# 6_CLOCK.net
KiCad netlist of a schematic drawn in Altium Designer
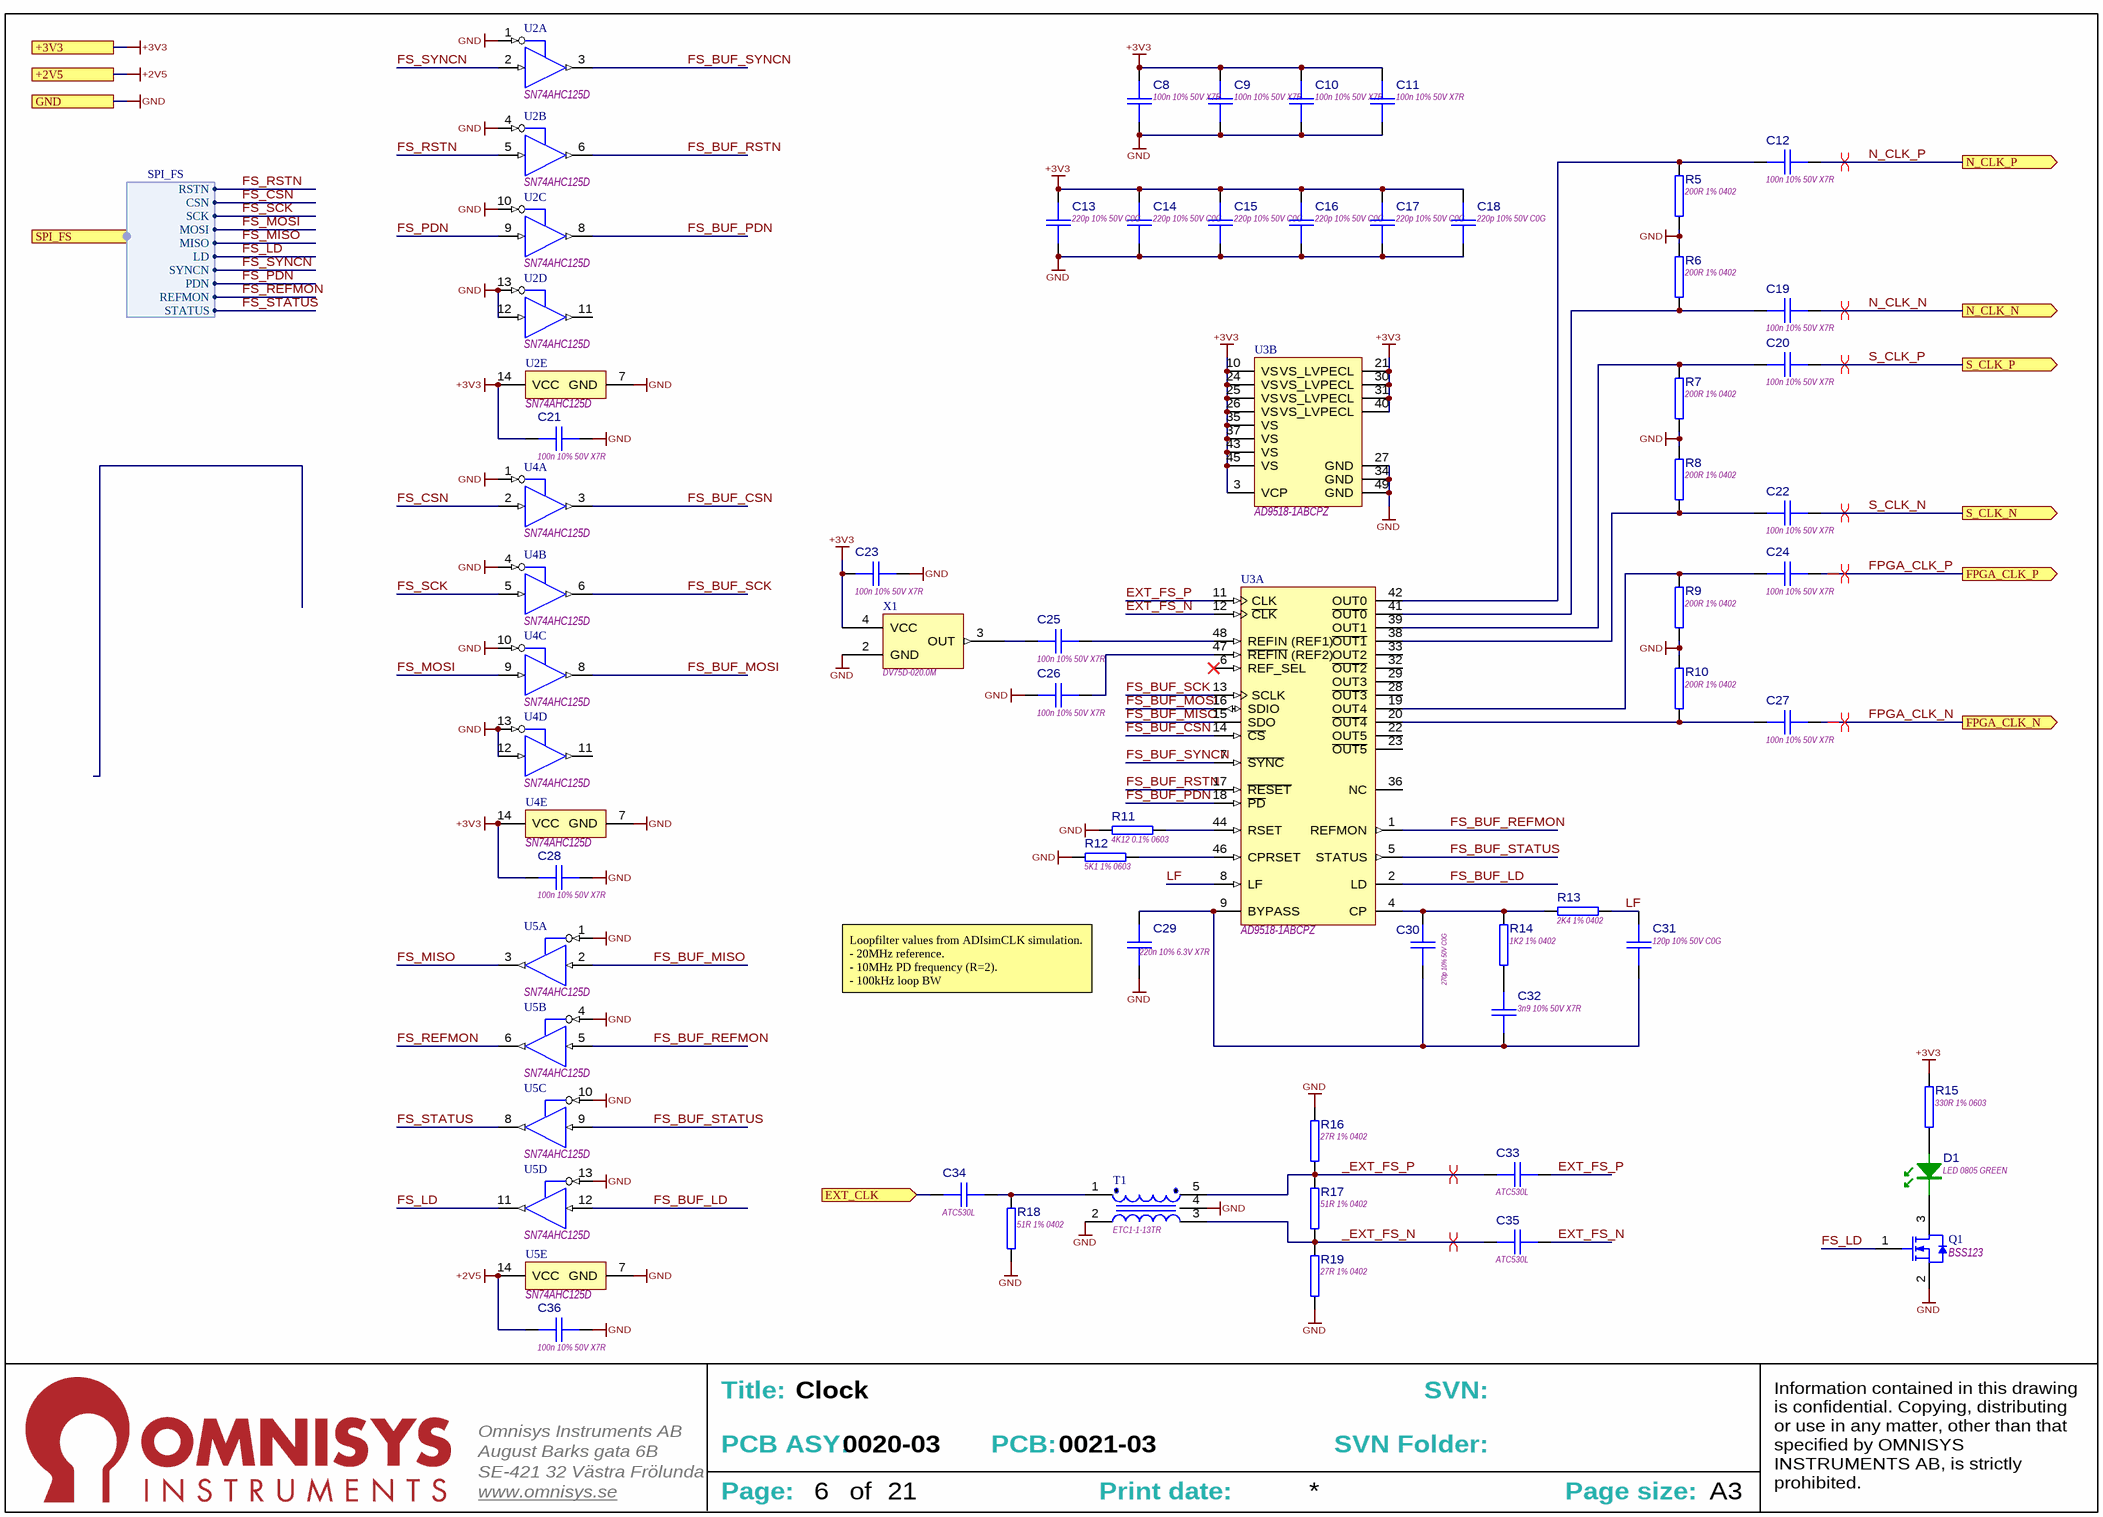
[diagram p0: [6] CLOCK.SchDoc]

(export (version "E")
  (design (tool "Eeschema 10.0.6"))
  (components
    (comp (ref "C8")
      (value "100n 10% 50V X7R")
      (footprint "CAPC1608X90N")
      (description "Ceramic Chip Capacitor, 0603/1608")
      (fields (field (name "TOLERANCE") "10%"))
      (libsource (lib "Omnisys Vault") (part "CAP-2PIN"))
    )
    (comp (ref "C9")
      (value "100n 10% 50V X7R")
      (footprint "CAPC1608X90N")
      (description "Ceramic Chip Capacitor, 0603/1608")
      (fields (field (name "TOLERANCE") "10%"))
      (libsource (lib "Omnisys Vault") (part "CAP-2PIN"))
    )
    (comp (ref "C10")
      (value "100n 10% 50V X7R")
      (footprint "CAPC1608X90N")
      (description "Ceramic Chip Capacitor, 0603/1608")
      (fields (field (name "TOLERANCE") "10%"))
      (libsource (lib "Omnisys Vault") (part "CAP-2PIN"))
    )
    (comp (ref "C11")
      (value "100n 10% 50V X7R")
      (footprint "CAPC1608X90N")
      (description "Ceramic Chip Capacitor, 0603/1608")
      (fields (field (name "TOLERANCE") "10%"))
      (libsource (lib "Omnisys Vault") (part "CAP-2PIN"))
    )
    (comp (ref "C12")
      (value "100n 10% 50V X7R")
      (footprint "CAPC1005X55L")
      (description "Ceramic Chip Capacitor, 0402/1005")
      (fields (field (name "TOLERANCE") "10%"))
      (libsource (lib "Omnisys Vault") (part "CAP-2PIN"))
    )
    (comp (ref "C13")
      (value "220p 10% 50V C0G")
      (footprint "CAPC1005X55N")
      (description "Ceramic Chip Capacitor, 0402/1005")
      (fields (field (name "TOLERANCE") "10%"))
      (libsource (lib "Omnisys Vault") (part "CAP-2PIN"))
    )
    (comp (ref "C14")
      (value "220p 10% 50V C0G")
      (footprint "CAPC1005X55N")
      (description "Ceramic Chip Capacitor, 0402/1005")
      (fields (field (name "TOLERANCE") "10%"))
      (libsource (lib "Omnisys Vault") (part "CAP-2PIN"))
    )
    (comp (ref "C15")
      (value "220p 10% 50V C0G")
      (footprint "CAPC1005X55N")
      (description "Ceramic Chip Capacitor, 0402/1005")
      (fields (field (name "TOLERANCE") "10%"))
      (libsource (lib "Omnisys Vault") (part "CAP-2PIN"))
    )
    (comp (ref "C16")
      (value "220p 10% 50V C0G")
      (footprint "CAPC1005X55N")
      (description "Ceramic Chip Capacitor, 0402/1005")
      (fields (field (name "TOLERANCE") "10%"))
      (libsource (lib "Omnisys Vault") (part "CAP-2PIN"))
    )
    (comp (ref "C17")
      (value "220p 10% 50V C0G")
      (footprint "CAPC1005X55N")
      (description "Ceramic Chip Capacitor, 0402/1005")
      (fields (field (name "TOLERANCE") "10%"))
      (libsource (lib "Omnisys Vault") (part "CAP-2PIN"))
    )
    (comp (ref "C18")
      (value "220p 10% 50V C0G")
      (footprint "CAPC1005X55N")
      (description "Ceramic Chip Capacitor, 0402/1005")
      (fields (field (name "TOLERANCE") "10%"))
      (libsource (lib "Omnisys Vault") (part "CAP-2PIN"))
    )
    (comp (ref "C19")
      (value "100n 10% 50V X7R")
      (footprint "CAPC1005X55L")
      (description "Ceramic Chip Capacitor, 0402/1005")
      (fields (field (name "TOLERANCE") "10%"))
      (libsource (lib "Omnisys Vault") (part "CAP-2PIN"))
    )
    (comp (ref "C20")
      (value "100n 10% 50V X7R")
      (footprint "CAPC1005X55L")
      (description "Ceramic Chip Capacitor, 0402/1005")
      (fields (field (name "TOLERANCE") "10%"))
      (libsource (lib "Omnisys Vault") (part "CAP-2PIN"))
    )
    (comp (ref "C21")
      (value "100n 10% 50V X7R")
      (footprint "CAPC1608X90N")
      (description "Ceramic Chip Capacitor, 0603/1608")
      (fields (field (name "TOLERANCE") "10%"))
      (libsource (lib "Omnisys Vault") (part "CAP-2PIN"))
    )
    (comp (ref "C22")
      (value "100n 10% 50V X7R")
      (footprint "CAPC1005X55L")
      (description "Ceramic Chip Capacitor, 0402/1005")
      (fields (field (name "TOLERANCE") "10%"))
      (libsource (lib "Omnisys Vault") (part "CAP-2PIN"))
    )
    (comp (ref "C23")
      (value "100n 10% 50V X7R")
      (footprint "CAPC1608X90N")
      (description "Ceramic Chip Capacitor, 0603/1608")
      (fields (field (name "TOLERANCE") "10%"))
      (libsource (lib "Omnisys Vault") (part "CAP-2PIN"))
    )
    (comp (ref "C24")
      (value "100n 10% 50V X7R")
      (footprint "CAPC1005X55L")
      (description "Ceramic Chip Capacitor, 0402/1005")
      (fields (field (name "TOLERANCE") "10%"))
      (libsource (lib "Omnisys Vault") (part "CAP-2PIN"))
    )
    (comp (ref "C25")
      (value "100n 10% 50V X7R")
      (footprint "CAPC1005X55L")
      (description "Ceramic Chip Capacitor, 0402/1005")
      (fields (field (name "TOLERANCE") "10%"))
      (libsource (lib "Omnisys Vault") (part "CAP-2PIN"))
    )
    (comp (ref "C26")
      (value "100n 10% 50V X7R")
      (footprint "CAPC1005X55L")
      (description "Ceramic Chip Capacitor, 0402/1005")
      (fields (field (name "TOLERANCE") "10%"))
      (libsource (lib "Omnisys Vault") (part "CAP-2PIN"))
    )
    (comp (ref "C27")
      (value "100n 10% 50V X7R")
      (footprint "CAPC1005X55L")
      (description "Ceramic Chip Capacitor, 0402/1005")
      (fields (field (name "TOLERANCE") "10%"))
      (libsource (lib "Omnisys Vault") (part "CAP-2PIN"))
    )
    (comp (ref "C28")
      (value "100n 10% 50V X7R")
      (footprint "CAPC1608X90N")
      (description "Ceramic Chip Capacitor, 0603/1608")
      (fields (field (name "TOLERANCE") "10%"))
      (libsource (lib "Omnisys Vault") (part "CAP-2PIN"))
    )
    (comp (ref "C29")
      (value "220n 10% 6.3V X7R")
      (footprint "CAPC1608X90L")
      (description "Ceramic Chip Capacitor, 0603/1608")
      (fields (field (name "TOLERANCE") "10%"))
      (libsource (lib "Omnisys Vault") (part "CAP-2PIN"))
    )
    (comp (ref "C30")
      (value "270p 10% 50V C0G")
      (footprint "CAPC1005X55L")
      (description "Ceramic Chip Capacitor, 0402/1005")
      (fields (field (name "TOLERANCE") "10%"))
      (libsource (lib "Omnisys Vault") (part "CAP-2PIN"))
    )
    (comp (ref "C31")
      (value "120p 10% 50V C0G")
      (footprint "CAPC1005X55L")
      (description "Ceramic Chip Capacitor, 0402/1005")
      (fields (field (name "TOLERANCE") "10%"))
      (libsource (lib "Omnisys Vault") (part "CAP-2PIN"))
    )
    (comp (ref "C32")
      (value "3n9 10% 50V X7R")
      (footprint "CAPC1005X55L")
      (description "Ceramic Chip Capacitor, 0402/1005")
      (fields (field (name "TOLERANCE") "10%"))
      (libsource (lib "Omnisys Vault") (part "CAP-2PIN"))
    )
    (comp (ref "C33")
      (value "ATC530L")
      (footprint "CAPC1005X06L")
      (description "100n 16V ±15% 0402 (1005 metric) ATC530L104KT16T")
      (fields (field (name "TOLERANCE") "±15%"))
      (libsource (lib "Omnisys Vault") (part "CAP-2PIN"))
    )
    (comp (ref "C34")
      (value "ATC530L")
      (footprint "CAPC1005X06L")
      (description "100n 16V ±15% 0402 (1005 metric) ATC530L104KT16T")
      (fields (field (name "TOLERANCE") "±15%"))
      (libsource (lib "Omnisys Vault") (part "CAP-2PIN"))
    )
    (comp (ref "C35")
      (value "ATC530L")
      (footprint "CAPC1005X06L")
      (description "100n 16V ±15% 0402 (1005 metric) ATC530L104KT16T")
      (fields (field (name "TOLERANCE") "±15%"))
      (libsource (lib "Omnisys Vault") (part "CAP-2PIN"))
    )
    (comp (ref "C36")
      (value "100n 10% 50V X7R")
      (footprint "CAPC1608X90N")
      (description "Ceramic Chip Capacitor, 0603/1608")
      (fields (field (name "TOLERANCE") "10%"))
      (libsource (lib "Omnisys Vault") (part "CAP-2PIN"))
    )
    (comp (ref "D1")
      (value "LED 0805 GREEN")
      (footprint "LED2012-GREEN")
      (libsource (lib "Omnisys Vault") (part "LED-2PIN-GREEN"))
    )
    (comp (ref "Q1")
      (value "BSS123")
      (footprint "SOT95P230X110-3N")
      (description "MOSFET N-CH 100V 170MA SOT-23")
      (fields (field (name "VOLTAGE") "100V"))
      (libsource (lib "Omnisys Vault") (part "NEMOS-GSD-3"))
    )
    (comp (ref "R5")
      (value "200R 1% 0402")
      (footprint "RESC1005L")
      (description "Thick film Chip Resistor, 0402/1005")
      (fields (field (name "POWER") "100mW") (field (name "TOLERANCE") "1%"))
      (libsource (lib "Omnisys Vault") (part "RES-2PIN"))
    )
    (comp (ref "R6")
      (value "200R 1% 0402")
      (footprint "RESC1005L")
      (description "Thick film Chip Resistor, 0402/1005")
      (fields (field (name "POWER") "100mW") (field (name "TOLERANCE") "1%"))
      (libsource (lib "Omnisys Vault") (part "RES-2PIN"))
    )
    (comp (ref "R7")
      (value "200R 1% 0402")
      (footprint "RESC1005L")
      (description "Thick film Chip Resistor, 0402/1005")
      (fields (field (name "POWER") "100mW") (field (name "TOLERANCE") "1%"))
      (libsource (lib "Omnisys Vault") (part "RES-2PIN"))
    )
    (comp (ref "R8")
      (value "200R 1% 0402")
      (footprint "RESC1005L")
      (description "Thick film Chip Resistor, 0402/1005")
      (fields (field (name "POWER") "100mW") (field (name "TOLERANCE") "1%"))
      (libsource (lib "Omnisys Vault") (part "RES-2PIN"))
    )
    (comp (ref "R9")
      (value "200R 1% 0402")
      (footprint "RESC1005L")
      (description "Thick film Chip Resistor, 0402/1005")
      (fields (field (name "POWER") "100mW") (field (name "TOLERANCE") "1%"))
      (libsource (lib "Omnisys Vault") (part "RES-2PIN"))
    )
    (comp (ref "R10")
      (value "200R 1% 0402")
      (footprint "RESC1005L")
      (description "Thick film Chip Resistor, 0402/1005")
      (fields (field (name "POWER") "100mW") (field (name "TOLERANCE") "1%"))
      (libsource (lib "Omnisys Vault") (part "RES-2PIN"))
    )
    (comp (ref "R11")
      (value "4K12 0.1% 0603")
      (footprint "RESC1608N")
      (description "Thin film Chip Resistor, 0603/1608")
      (fields (field (name "POWER") "100mW") (field (name "TOLERANCE") "0.1%"))
      (libsource (lib "Omnisys Vault") (part "RES-2PIN"))
    )
    (comp (ref "R12")
      (value "5K1 1% 0603")
      (footprint "RESC1608N")
      (description "Thick film Chip Resistor, 0603/1608")
      (fields (field (name "POWER") "100mW") (field (name "TOLERANCE") "1%"))
      (libsource (lib "Omnisys Vault") (part "RES-2PIN"))
    )
    (comp (ref "R13")
      (value "2K4 1% 0402")
      (footprint "RESC1005L")
      (description "Thick film Chip Resistor, 0402/1005")
      (fields (field (name "POWER") "100mW") (field (name "TOLERANCE") "1%"))
      (libsource (lib "Omnisys Vault") (part "RES-2PIN"))
    )
    (comp (ref "R14")
      (value "1K2 1% 0402")
      (footprint "RESC1005L")
      (description "Thick film Chip Resistor, 0402/1005")
      (fields (field (name "POWER") "100mW") (field (name "TOLERANCE") "1%"))
      (libsource (lib "Omnisys Vault") (part "RES-2PIN"))
    )
    (comp (ref "R15")
      (value "330R 1% 0603")
      (footprint "RESC1608N")
      (description "Thick film Chip Resistor, 0603/1608")
      (fields (field (name "POWER") "100mW") (field (name "TOLERANCE") "1%"))
      (libsource (lib "Omnisys Vault") (part "RES-2PIN"))
    )
    (comp (ref "R16")
      (value "27R 1% 0402")
      (footprint "RESC1005L")
      (description "Thick film Chip Resistor, 0402/1005")
      (fields (field (name "POWER") "100mW") (field (name "TOLERANCE") "1%"))
      (libsource (lib "Omnisys Vault") (part "RES-2PIN"))
    )
    (comp (ref "R17")
      (value "51R 1% 0402")
      (footprint "RESC1005L")
      (description "Thick film Chip Resistor, 0402/1005")
      (fields (field (name "POWER") "100mW") (field (name "TOLERANCE") "1%"))
      (libsource (lib "Omnisys Vault") (part "RES-2PIN"))
    )
    (comp (ref "R18")
      (value "51R 1% 0402")
      (footprint "RESC1005L")
      (description "Thick film Chip Resistor, 0402/1005")
      (fields (field (name "POWER") "100mW") (field (name "TOLERANCE") "1%"))
      (libsource (lib "Omnisys Vault") (part "RES-2PIN"))
    )
    (comp (ref "R19")
      (value "27R 1% 0402")
      (footprint "RESC1005L")
      (description "Thick film Chip Resistor, 0402/1005")
      (fields (field (name "POWER") "100mW") (field (name "TOLERANCE") "1%"))
      (libsource (lib "Omnisys Vault") (part "RES-2PIN"))
    )
    (comp (ref "T1")
      (value "ETC1-1-13TR")
      (footprint "SOTFL50P160X73-3N")
      (description "Transformers Audio & Signal 4.5-3000MHz IL 2dB Impedance Ratio 1:1")
      (libsource (lib "Omnisys Vault") (part "ETC1-1-13TR"))
    )
    (comp (ref "U2")
      (value "SN74AHC125D")
      (footprint "SOIC127P600X175-14N")
      (description "Buffer/Line Driver 4-CH Non-Inverting 3-ST CMOS 14-Pin SOIC Tube")
      (libsource (lib "Omnisys Vault") (part "SN74AHC125D"))
    )
    (comp (ref "U3")
      (value "AD9518-1ABCPZ")
      (footprint "ADI-CP-48-8_M")
      (description "IC CLOCK GEN 6CH 2.65GHZ 48LFCSP")
      (libsource (lib "Omnisys Vault") (part "ADI-AD9518-1-CP-48-8"))
    )
    (comp (ref "U4")
      (value "SN74AHC125D")
      (footprint "SOIC127P600X175-14N")
      (description "Buffer/Line Driver 4-CH Non-Inverting 3-ST CMOS 14-Pin SOIC Tube")
      (libsource (lib "Omnisys Vault") (part "SN74AHC125D"))
    )
    (comp (ref "U5")
      (value "SN74AHC125D")
      (footprint "SOIC127P600X175-14N")
      (description "Buffer/Line Driver 4-CH Non-Inverting 3-ST CMOS 14-Pin SOIC Tube")
      (libsource (lib "Omnisys Vault") (part "SN74AHC125D"))
    )
    (comp (ref "X1")
      (value "DV75D-020.0M")
      (footprint "DV75D")
      (description "OSC TCXO 20.000MHZ LVCMOS SMD")
      (libsource (lib "Omnisys Vault") (part "DV75D-020.0M"))
    )
  )
  (nets
    (net (code "2") (name "+2V5") (class "Default")
      (node (ref "C36") (pin "2") (pinfunction "2_2") (pintype "passive"))
      (node (ref "U5") (pin "14") (pinfunction "VCC_14") (pintype "power_in"))
    )
    (net (code "3") (name "+3V3") (class "Default")
      (node (ref "C10") (pin "2") (pinfunction "2_2") (pintype "passive"))
      (node (ref "C11") (pin "2") (pinfunction "2_2") (pintype "passive"))
      (node (ref "C13") (pin "2") (pinfunction "2_2") (pintype "passive"))
      (node (ref "C14") (pin "2") (pinfunction "2_2") (pintype "passive"))
      (node (ref "C15") (pin "2") (pinfunction "2_2") (pintype "passive"))
      (node (ref "C16") (pin "2") (pinfunction "2_2") (pintype "passive"))
      (node (ref "C17") (pin "2") (pinfunction "2_2") (pintype "passive"))
      (node (ref "C18") (pin "2") (pinfunction "2_2") (pintype "passive"))
      (node (ref "C21") (pin "2") (pinfunction "2_2") (pintype "passive"))
      (node (ref "C23") (pin "2") (pinfunction "2_2") (pintype "passive"))
      (node (ref "C28") (pin "2") (pinfunction "2_2") (pintype "passive"))
      (node (ref "C8") (pin "2") (pinfunction "2_2") (pintype "passive"))
      (node (ref "C9") (pin "2") (pinfunction "2_2") (pintype "passive"))
      (node (ref "R15") (pin "2") (pinfunction "2_2") (pintype "passive"))
      (node (ref "U2") (pin "14") (pinfunction "VCC_14") (pintype "power_in"))
      (node (ref "U3") (pin "10") (pinfunction "VS_10") (pintype "power_in"))
      (node (ref "U3") (pin "21") (pinfunction "VS_LVPECL_21") (pintype "power_in"))
      (node (ref "U3") (pin "24") (pinfunction "VS_24") (pintype "power_in"))
      (node (ref "U3") (pin "25") (pinfunction "VS_25") (pintype "power_in"))
      (node (ref "U3") (pin "26") (pinfunction "VS_26") (pintype "power_in"))
      (node (ref "U3") (pin "3") (pinfunction "VCP_3") (pintype "power_in"))
      (node (ref "U3") (pin "30") (pinfunction "VS_LVPECL_30") (pintype "power_in"))
      (node (ref "U3") (pin "31") (pinfunction "VS_LVPECL_31") (pintype "power_in"))
      (node (ref "U3") (pin "35") (pinfunction "VS_35") (pintype "power_in"))
      (node (ref "U3") (pin "37") (pinfunction "VS_37") (pintype "power_in"))
      (node (ref "U3") (pin "40") (pinfunction "VS_LVPECL_40") (pintype "power_in"))
      (node (ref "U3") (pin "43") (pinfunction "VS_43") (pintype "power_in"))
      (node (ref "U3") (pin "45") (pinfunction "VS_45") (pintype "power_in"))
      (node (ref "U4") (pin "14") (pinfunction "VCC_14") (pintype "power_in"))
      (node (ref "X1") (pin "4") (pinfunction "VCC_4") (pintype "power_in"))
    )
    (net (code "4") (name "/EXT_CLK") (class "Default")
      (node (ref "C34") (pin "1") (pinfunction "1_1") (pintype "passive"))
    )
    (net (code "5") (name "/EXT_FS_N") (class "Default")
      (node (ref "C35") (pin "2") (pinfunction "2_2") (pintype "passive"))
      (node (ref "U3") (pin "12") (pinfunction "~{CLK}_12") (pintype "input"))
    )
    (net (code "6") (name "/EXT_FS_P") (class "Default")
      (node (ref "C33") (pin "2") (pinfunction "2_2") (pintype "passive"))
      (node (ref "U3") (pin "11") (pinfunction "CLK_11") (pintype "input"))
    )
    (net (code "7") (name "/FPGA_CLK_N") (class "Default")
      (node (ref "C27") (pin "1") (pinfunction "1_1") (pintype "passive"))
    )
    (net (code "8") (name "/FPGA_CLK_P") (class "Default")
      (node (ref "C24") (pin "1") (pinfunction "1_1") (pintype "passive"))
    )
    (net (code "9") (name "/FS_BUF_CSN") (class "Default")
      (node (ref "U3") (pin "14") (pinfunction "~{CS}_14") (pintype "input"))
      (node (ref "U4") (pin "3") (pinfunction "1Y_3") (pintype "output"))
    )
    (net (code "10") (name "/FS_BUF_LD") (class "Default")
      (node (ref "U3") (pin "2") (pinfunction "LD_2") (pintype "tri_state"))
      (node (ref "U5") (pin "12") (pinfunction "4A_12") (pintype "input"))
    )
    (net (code "11") (name "/FS_BUF_MISO") (class "Default")
      (node (ref "U3") (pin "15") (pinfunction "SDO_15") (pintype "tri_state"))
      (node (ref "U5") (pin "2") (pinfunction "1A_2") (pintype "input"))
    )
    (net (code "12") (name "/FS_BUF_MOSI") (class "Default")
      (node (ref "U3") (pin "16") (pinfunction "SDIO_16") (pintype "bidirectional"))
      (node (ref "U4") (pin "8") (pinfunction "3Y_8") (pintype "output"))
    )
    (net (code "13") (name "/FS_BUF_PDN") (class "Default")
      (node (ref "U2") (pin "8") (pinfunction "3Y_8") (pintype "output"))
      (node (ref "U3") (pin "18") (pinfunction "~{PD}_18") (pintype "input"))
    )
    (net (code "14") (name "/FS_BUF_REFMON") (class "Default")
      (node (ref "U3") (pin "1") (pinfunction "REFMON_1") (pintype "output"))
      (node (ref "U5") (pin "5") (pinfunction "2A_5") (pintype "input"))
    )
    (net (code "15") (name "/FS_BUF_RSTN") (class "Default")
      (node (ref "U2") (pin "6") (pinfunction "2Y_6") (pintype "output"))
      (node (ref "U3") (pin "17") (pinfunction "~{RESET}_17") (pintype "input"))
    )
    (net (code "16") (name "/FS_BUF_SCK") (class "Default")
      (node (ref "U3") (pin "13") (pinfunction "SCLK_13") (pintype "input"))
      (node (ref "U4") (pin "6") (pinfunction "2Y_6") (pintype "output"))
    )
    (net (code "17") (name "/FS_BUF_STATUS") (class "Default")
      (node (ref "U3") (pin "5") (pinfunction "STATUS_5") (pintype "output"))
      (node (ref "U5") (pin "9") (pinfunction "3A_9") (pintype "input"))
    )
    (net (code "18") (name "/FS_BUF_SYNCN") (class "Default")
      (node (ref "U2") (pin "3") (pinfunction "1Y_3") (pintype "output"))
      (node (ref "U3") (pin "7") (pinfunction "~{SYNC}_7") (pintype "input"))
    )
    (net (code "19") (name "/FS_CSN") (class "Default")
      (node (ref "U4") (pin "2") (pinfunction "1A_2") (pintype "input"))
    )
    (net (code "20") (name "/FS_LD") (class "Default")
      (node (ref "Q1") (pin "1") (pinfunction "G_1") (pintype "passive"))
      (node (ref "U5") (pin "11") (pinfunction "4Y_11") (pintype "output"))
    )
    (net (code "21") (name "/FS_MISO") (class "Default")
      (node (ref "U5") (pin "3") (pinfunction "1Y_3") (pintype "output"))
    )
    (net (code "22") (name "/FS_MOSI") (class "Default")
      (node (ref "U4") (pin "9") (pinfunction "3A_9") (pintype "input"))
    )
    (net (code "23") (name "/FS_PDN") (class "Default")
      (node (ref "U2") (pin "9") (pinfunction "3A_9") (pintype "input"))
    )
    (net (code "24") (name "/FS_REFMON") (class "Default")
      (node (ref "U5") (pin "6") (pinfunction "2Y_6") (pintype "output"))
    )
    (net (code "25") (name "/FS_RSTN") (class "Default")
      (node (ref "U2") (pin "5") (pinfunction "2A_5") (pintype "input"))
    )
    (net (code "26") (name "/FS_SCK") (class "Default")
      (node (ref "U4") (pin "5") (pinfunction "2A_5") (pintype "input"))
    )
    (net (code "27") (name "/FS_STATUS") (class "Default")
      (node (ref "U5") (pin "8") (pinfunction "3Y_8") (pintype "output"))
    )
    (net (code "28") (name "/FS_SYNCN") (class "Default")
      (node (ref "U2") (pin "2") (pinfunction "1A_2") (pintype "input"))
    )
    (net (code "29") (name "/LF") (class "Default")
      (node (ref "C31") (pin "2") (pinfunction "2_2") (pintype "passive"))
      (node (ref "R13") (pin "2") (pinfunction "2_2") (pintype "passive"))
      (node (ref "U3") (pin "8") (pinfunction "LF_8") (pintype "input"))
    )
    (net (code "30") (name "/N_CLK_N") (class "Default")
      (node (ref "C19") (pin "1") (pinfunction "1_1") (pintype "passive"))
    )
    (net (code "31") (name "/N_CLK_P") (class "Default")
      (node (ref "C12") (pin "1") (pinfunction "1_1") (pintype "passive"))
    )
    (net (code "32") (name "/S_CLK_N") (class "Default")
      (node (ref "C22") (pin "1") (pinfunction "1_1") (pintype "passive"))
    )
    (net (code "33") (name "/S_CLK_P") (class "Default")
      (node (ref "C20") (pin "1") (pinfunction "1_1") (pintype "passive"))
    )
    (net (code "34") (name "/_EXT_FS_N") (class "Default")
      (node (ref "C35") (pin "1") (pinfunction "1_1") (pintype "passive"))
      (node (ref "R17") (pin "1") (pinfunction "1_1") (pintype "passive"))
      (node (ref "R19") (pin "1") (pinfunction "1_1") (pintype "passive"))
      (node (ref "T1") (pin "3") (pinfunction "Secondary_3") (pintype "passive"))
    )
    (net (code "35") (name "/_EXT_FS_P") (class "Default")
      (node (ref "C33") (pin "1") (pinfunction "1_1") (pintype "passive"))
      (node (ref "R16") (pin "1") (pinfunction "1_1") (pintype "passive"))
      (node (ref "R17") (pin "2") (pinfunction "2_2") (pintype "passive"))
      (node (ref "T1") (pin "5") (pinfunction "Secondary_dot_5") (pintype "passive"))
    )
    (net (code "37") (name "GND") (class "Default")
      (node (ref "C10") (pin "1") (pinfunction "1_1") (pintype "passive"))
      (node (ref "C11") (pin "1") (pinfunction "1_1") (pintype "passive"))
      (node (ref "C13") (pin "1") (pinfunction "1_1") (pintype "passive"))
      (node (ref "C14") (pin "1") (pinfunction "1_1") (pintype "passive"))
      (node (ref "C15") (pin "1") (pinfunction "1_1") (pintype "passive"))
      (node (ref "C16") (pin "1") (pinfunction "1_1") (pintype "passive"))
      (node (ref "C17") (pin "1") (pinfunction "1_1") (pintype "passive"))
      (node (ref "C18") (pin "1") (pinfunction "1_1") (pintype "passive"))
      (node (ref "C21") (pin "1") (pinfunction "1_1") (pintype "passive"))
      (node (ref "C23") (pin "1") (pinfunction "1_1") (pintype "passive"))
      (node (ref "C26") (pin "2") (pinfunction "2_2") (pintype "passive"))
      (node (ref "C28") (pin "1") (pinfunction "1_1") (pintype "passive"))
      (node (ref "C29") (pin "2") (pinfunction "2_2") (pintype "passive"))
      (node (ref "C36") (pin "1") (pinfunction "1_1") (pintype "passive"))
      (node (ref "C8") (pin "1") (pinfunction "1_1") (pintype "passive"))
      (node (ref "C9") (pin "1") (pinfunction "1_1") (pintype "passive"))
      (node (ref "Q1") (pin "2") (pinfunction "S_2") (pintype "passive"))
      (node (ref "R10") (pin "2") (pinfunction "2_2") (pintype "passive"))
      (node (ref "R11") (pin "1") (pinfunction "1_1") (pintype "passive"))
      (node (ref "R12") (pin "1") (pinfunction "1_1") (pintype "passive"))
      (node (ref "R16") (pin "2") (pinfunction "2_2") (pintype "passive"))
      (node (ref "R18") (pin "2") (pinfunction "2_2") (pintype "passive"))
      (node (ref "R19") (pin "2") (pinfunction "2_2") (pintype "passive"))
      (node (ref "R5") (pin "2") (pinfunction "2_2") (pintype "passive"))
      (node (ref "R6") (pin "2") (pinfunction "2_2") (pintype "passive"))
      (node (ref "R7") (pin "2") (pinfunction "2_2") (pintype "passive"))
      (node (ref "R8") (pin "2") (pinfunction "2_2") (pintype "passive"))
      (node (ref "R9") (pin "2") (pinfunction "2_2") (pintype "passive"))
      (node (ref "T1") (pin "2") (pinfunction "Primary_2") (pintype "passive"))
      (node (ref "T1") (pin "4") (pinfunction "NC_4") (pintype "passive"))
      (node (ref "U2") (pin "1") (pinfunction "1OE#_1") (pintype "input"))
      (node (ref "U2") (pin "10") (pinfunction "3OE#_10") (pintype "input"))
      (node (ref "U2") (pin "12") (pinfunction "4A_12") (pintype "input"))
      (node (ref "U2") (pin "13") (pinfunction "4OE#_13") (pintype "input"))
      (node (ref "U2") (pin "4") (pinfunction "2OE#_4") (pintype "input"))
      (node (ref "U2") (pin "7") (pinfunction "GND_7") (pintype "power_in"))
      (node (ref "U3") (pin "27") (pinfunction "GND_27") (pintype "power_in"))
      (node (ref "U3") (pin "34") (pinfunction "GND_34") (pintype "power_in"))
      (node (ref "U3") (pin "49") (pinfunction "GND_49") (pintype "power_in"))
      (node (ref "U4") (pin "1") (pinfunction "1OE#_1") (pintype "input"))
      (node (ref "U4") (pin "10") (pinfunction "3OE#_10") (pintype "input"))
      (node (ref "U4") (pin "12") (pinfunction "4A_12") (pintype "input"))
      (node (ref "U4") (pin "13") (pinfunction "4OE#_13") (pintype "input"))
      (node (ref "U4") (pin "4") (pinfunction "2OE#_4") (pintype "input"))
      (node (ref "U4") (pin "7") (pinfunction "GND_7") (pintype "power_in"))
      (node (ref "U5") (pin "1") (pinfunction "1OE#_1") (pintype "input"))
      (node (ref "U5") (pin "10") (pinfunction "3OE#_10") (pintype "input"))
      (node (ref "U5") (pin "13") (pinfunction "4OE#_13") (pintype "input"))
      (node (ref "U5") (pin "4") (pinfunction "2OE#_4") (pintype "input"))
      (node (ref "U5") (pin "7") (pinfunction "GND_7") (pintype "power_in"))
      (node (ref "X1") (pin "2") (pinfunction "GND_2") (pintype "power_in"))
    )
    (net (code "38") (name "Net-(C32-Pad1)") (class "Default")
      (node (ref "C32") (pin "1") (pinfunction "1_1") (pintype "passive"))
      (node (ref "R14") (pin "1") (pinfunction "1_1") (pintype "passive"))
    )
    (net (code "39") (name "Net-(D1-Pad2)") (class "Default")
      (node (ref "D1") (pin "2") (pintype "passive"))
      (node (ref "R15") (pin "1") (pinfunction "1_1") (pintype "passive"))
    )
    (net (code "40") (name "Net-(Q1-D)") (class "Default")
      (node (ref "D1") (pin "1") (pintype "passive"))
      (node (ref "Q1") (pin "3") (pinfunction "D_3") (pintype "passive"))
    )
    (net (code "41") (name "Net-(T1-Primary_dot)") (class "Default")
      (node (ref "C34") (pin "2") (pinfunction "2_2") (pintype "passive"))
      (node (ref "R18") (pin "1") (pinfunction "1_1") (pintype "passive"))
      (node (ref "T1") (pin "1") (pinfunction "Primary_dot_1") (pintype "passive"))
    )
    (net (code "42") (name "Net-(U3A-BYPASS)") (class "Default")
      (node (ref "C29") (pin "1") (pinfunction "1_1") (pintype "passive"))
      (node (ref "C30") (pin "2") (pinfunction "2_2") (pintype "passive"))
      (node (ref "C31") (pin "1") (pinfunction "1_1") (pintype "passive"))
      (node (ref "C32") (pin "2") (pinfunction "2_2") (pintype "passive"))
      (node (ref "U3") (pin "9") (pinfunction "BYPASS_9") (pintype "passive"))
    )
    (net (code "43") (name "Net-(U3A-CP)") (class "Default")
      (node (ref "C30") (pin "1") (pinfunction "1_1") (pintype "passive"))
      (node (ref "R13") (pin "1") (pinfunction "1_1") (pintype "passive"))
      (node (ref "R14") (pin "2") (pinfunction "2_2") (pintype "passive"))
      (node (ref "U3") (pin "4") (pinfunction "CP_4") (pintype "tri_state"))
    )
    (net (code "44") (name "Net-(U3A-CPRSET)") (class "Default")
      (node (ref "R12") (pin "2") (pinfunction "2_2") (pintype "passive"))
      (node (ref "U3") (pin "46") (pinfunction "CPRSET_46") (pintype "input"))
    )
    (net (code "45") (name "Net-(U3A-OUT0)") (class "Default")
      (node (ref "C12") (pin "2") (pinfunction "2_2") (pintype "passive"))
      (node (ref "R5") (pin "1") (pinfunction "1_1") (pintype "passive"))
      (node (ref "U3") (pin "42") (pinfunction "OUT0_42") (pintype "tri_state"))
    )
    (net (code "46") (name "Net-(U3A-OUT1)") (class "Default")
      (node (ref "C20") (pin "2") (pinfunction "2_2") (pintype "passive"))
      (node (ref "R7") (pin "1") (pinfunction "1_1") (pintype "passive"))
      (node (ref "U3") (pin "39") (pinfunction "OUT1_39") (pintype "tri_state"))
    )
    (net (code "47") (name "Net-(U3A-OUT4)") (class "Default")
      (node (ref "C24") (pin "2") (pinfunction "2_2") (pintype "passive"))
      (node (ref "R9") (pin "1") (pinfunction "1_1") (pintype "passive"))
      (node (ref "U3") (pin "19") (pinfunction "OUT4_19") (pintype "tri_state"))
    )
    (net (code "48") (name "Net-(U3A-REFIN_(REF1))") (class "Default")
      (node (ref "C25") (pin "1") (pinfunction "1_1") (pintype "passive"))
      (node (ref "U3") (pin "48") (pinfunction "REFIN_(REF1)_48") (pintype "input"))
    )
    (net (code "49") (name "Net-(U3A-RSET)") (class "Default")
      (node (ref "R11") (pin "2") (pinfunction "2_2") (pintype "passive"))
      (node (ref "U3") (pin "44") (pinfunction "RSET_44") (pintype "input"))
    )
    (net (code "50") (name "Net-(U3A-~{OUT0})") (class "Default")
      (node (ref "C19") (pin "2") (pinfunction "2_2") (pintype "passive"))
      (node (ref "R6") (pin "1") (pinfunction "1_1") (pintype "passive"))
      (node (ref "U3") (pin "41") (pinfunction "~{OUT0}_41") (pintype "tri_state"))
    )
    (net (code "51") (name "Net-(U3A-~{OUT1})") (class "Default")
      (node (ref "C22") (pin "2") (pinfunction "2_2") (pintype "passive"))
      (node (ref "R8") (pin "1") (pinfunction "1_1") (pintype "passive"))
      (node (ref "U3") (pin "38") (pinfunction "~{OUT1}_38") (pintype "tri_state"))
    )
    (net (code "52") (name "Net-(U3A-~{OUT4})") (class "Default")
      (node (ref "C27") (pin "2") (pinfunction "2_2") (pintype "passive"))
      (node (ref "R10") (pin "1") (pinfunction "1_1") (pintype "passive"))
      (node (ref "U3") (pin "20") (pinfunction "~{OUT4}_20") (pintype "tri_state"))
    )
    (net (code "53") (name "Net-(U3A-~{REFIN}_(REF2))") (class "Default")
      (node (ref "C26") (pin "1") (pinfunction "1_1") (pintype "passive"))
      (node (ref "U3") (pin "47") (pinfunction "~{REFIN}_(REF2)_47") (pintype "input"))
    )
    (net (code "54") (name "Net-(X1-OUT)") (class "Default")
      (node (ref "C25") (pin "2") (pinfunction "2_2") (pintype "passive"))
      (node (ref "X1") (pin "3") (pinfunction "OUT_3") (pintype "output"))
    )
    (net (code "55") (name "unconnected-(U2D-4Y-Pad11)") (class "Default")
      (node (ref "U2") (pin "11") (pinfunction "4Y_11") (pintype "output"))
    )
    (net (code "56") (name "unconnected-(U3A-NC-Pad36)") (class "Default")
      (node (ref "U3") (pin "36") (pinfunction "NC_36") (pintype "passive"))
    )
    (net (code "57") (name "unconnected-(U3A-OUT2-Pad33)") (class "Default")
      (node (ref "U3") (pin "33") (pinfunction "OUT2_33") (pintype "tri_state"))
    )
    (net (code "58") (name "unconnected-(U3A-OUT3-Pad29)") (class "Default")
      (node (ref "U3") (pin "29") (pinfunction "OUT3_29") (pintype "tri_state"))
    )
    (net (code "59") (name "unconnected-(U3A-OUT5-Pad22)") (class "Default")
      (node (ref "U3") (pin "22") (pinfunction "OUT5_22") (pintype "tri_state"))
    )
    (net (code "60") (name "unconnected-(U3A-REF_SEL-Pad6)") (class "Default")
      (node (ref "U3") (pin "6") (pinfunction "REF_SEL_6") (pintype "input+no_connect"))
    )
    (net (code "61") (name "unconnected-(U3A-~{OUT2}-Pad32)") (class "Default")
      (node (ref "U3") (pin "32") (pinfunction "~{OUT2}_32") (pintype "tri_state"))
    )
    (net (code "62") (name "unconnected-(U3A-~{OUT3}-Pad28)") (class "Default")
      (node (ref "U3") (pin "28") (pinfunction "~{OUT3}_28") (pintype "tri_state"))
    )
    (net (code "63") (name "unconnected-(U3A-~{OUT5}-Pad23)") (class "Default")
      (node (ref "U3") (pin "23") (pinfunction "~{OUT5}_23") (pintype "tri_state"))
    )
    (net (code "64") (name "unconnected-(U4D-4Y-Pad11)") (class "Default")
      (node (ref "U4") (pin "11") (pinfunction "4Y_11") (pintype "output"))
    )
  )
)
